# Standard_Header.net
KiCad netlist of a schematic drawn in Altium Designer
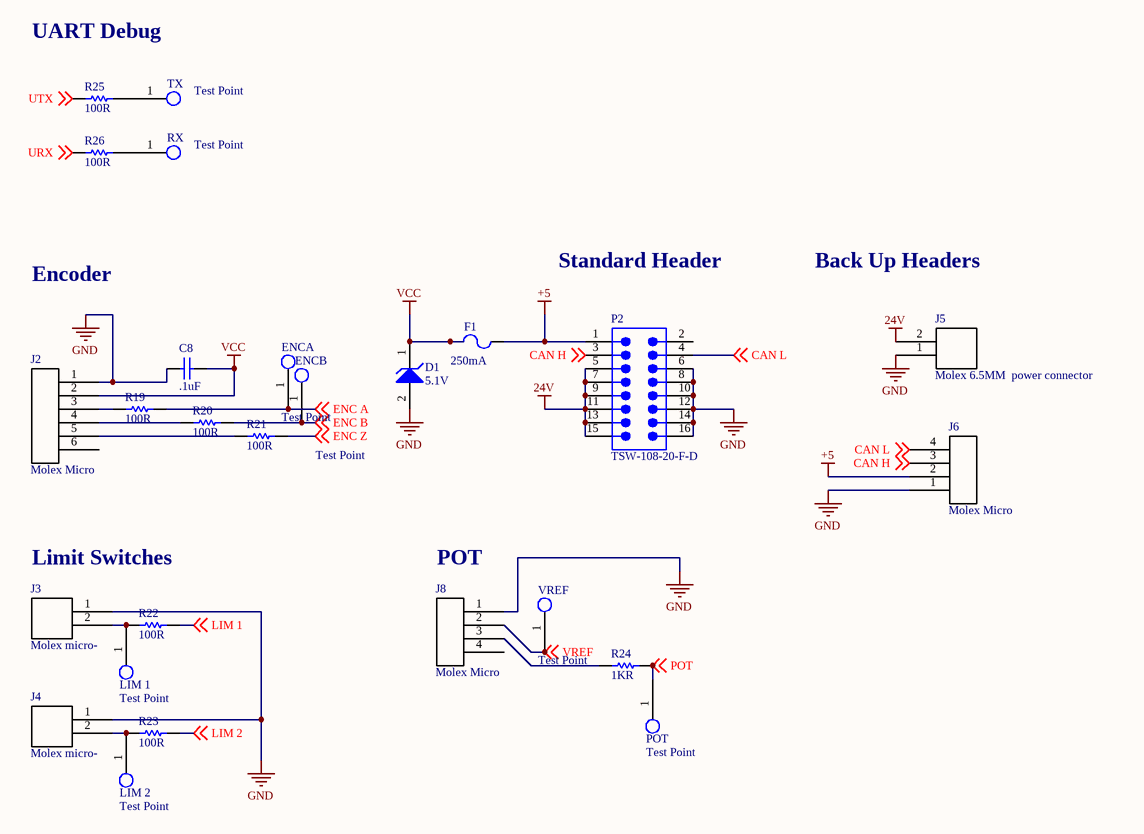
[diagram p0: Standard Header.SchDoc]

(export (version "E")
  (design (tool "Eeschema 10.0.6"))
  (components
    (comp (ref "C8")
      (value ".1uF")
      (footprint "CAPC0805(2012)130_N")
      (description "CAP 390pF 200V ±5% 0805 (2012 Metric) Thickness 1.3mm SMD")
      (fields (field (name "TOLERANCE") "Â±5%"))
      (libsource (lib "Altium Content Vault") (part "CAP"))
    )
    (comp (ref "D1")
      (value "5.1V")
      (footprint "ONSC-SMB-2-403A-03_H_V")
      (description "3 W Zener Voltage Regulator, 2-Pin SMB, Pb-Free, Tape and Reel")
      (fields (field (name "PARTNUMBER") "1SMB5917BT3G") (field (name "MANUFACTURER") "On Semiconductor"))
      (libsource (lib "Husky Robotics Standard Library 2019-2020") (part "CMP-1060-00195-1"))
    )
    (comp (ref "ENCA")
      (value "Test Point")
      (footprint "Test Point Through-hole")
      (libsource (lib "Husky Robotics Standard Library 2019-2020") (part "Test Point"))
    )
    (comp (ref "ENCB")
      (value "Test Point")
      (footprint "Test Point Through-hole")
      (libsource (lib "Husky Robotics Standard Library 2019-2020") (part "Test Point"))
    )
    (comp (ref "F1")
      (value "250mA")
      (footprint "BOUR-MF-NSMF150-2_V")
      (description "PTC Resettable Fuse, 6 V, 100 A, -40 to 85 degC, 2-Pin SMD, RoHS, Tape and Reel")
      (fields (field (name "MANUFACTURER") "Bourns"))
      (libsource (lib "Altium Content Vault") (part "FUSE-2"))
    )
    (comp (ref "J2")
      (value "Molex Micro")
      (footprint "0430450627")
      (description "Molex micro-fit 3.0 dual row connector. P/N 0430450627")
      (libsource (lib "Husky Robotics Standard Library 2019-2020") (part "Molex micro-fit 6-pin (single row schematic)"))
    )
    (comp (ref "J3")
      (value "Molex micro-")
      (footprint "0430450227")
      (description "Molex micro-fit 3.0. Molex P/N 0430450227")
      (libsource (lib "Husky Robotics Standard Library 2019-2020") (part "Molex micro-fit 2-pin"))
    )
    (comp (ref "J4")
      (value "Molex micro-")
      (footprint "0430450227")
      (description "Molex micro-fit 3.0. Molex P/N 0430450227")
      (libsource (lib "Husky Robotics Standard Library 2019-2020") (part "Molex micro-fit 2-pin"))
    )
    (comp (ref "J5")
      (value "Molex 6.5MM  power connector")
      (footprint "1510482204")
      (libsource (lib "Husky Robotics Standard Library 2019-2020") (part "Molex 6.5MM  power connector"))
    )
    (comp (ref "J6")
      (value "Molex Micro")
      (footprint "0430450427")
      (description "Molex micro-fit 3.0 dual row header. P/N 0430450427")
      (libsource (lib "Husky Robotics Standard Library 2019-2020") (part "Molex micro-fit 4-pin (Single row schematic)"))
    )
    (comp (ref "J8")
      (value "Molex Micro")
      (footprint "0430450427")
      (description "Molex micro-fit 3.0 dual row header. P/N 0430450427")
      (libsource (lib "Husky Robotics Standard Library 2019-2020") (part "Molex micro-fit 4-pin (Single row schematic)"))
    )
    (comp (ref "LIM 1")
      (value "Test Point")
      (footprint "Test Point Through-hole")
      (libsource (lib "Husky Robotics Standard Library 2019-2020") (part "Test Point"))
    )
    (comp (ref "LIM 2")
      (value "Test Point")
      (footprint "Test Point Through-hole")
      (libsource (lib "Husky Robotics Standard Library 2019-2020") (part "Test Point"))
    )
    (comp (ref "P2")
      (value "TSW-108-20-F-D")
      (footprint "SMTC-TSW-108-20-X-D")
      (fields (field (name "MANUFACTURER") "Samtec"))
      (libsource (lib "Altium Content Vault") (part "SMTC-TSW-108-X-X-D"))
    )
    (comp (ref "POT")
      (value "Test Point")
      (footprint "Test Point Through-hole")
      (libsource (lib "Husky Robotics Standard Library 2019-2020") (part "Test Point"))
    )
    (comp (ref "R19")
      (value "100R")
      (footprint "RESC0805(2012)_N")
      (description "120R 0.125W 5% 0805 (2012 Metric)  SMD")
      (fields (field (name "TOLERANCE") "5 %") (field (name "POWER") "0.125 W"))
      (libsource (lib "Husky Robotics Standard Library 2019-2020") (part "120R 5% 0805"))
    )
    (comp (ref "R20")
      (value "100R")
      (footprint "RESC0805(2012)_N")
      (description "120R 0.125W 5% 0805 (2012 Metric)  SMD")
      (fields (field (name "TOLERANCE") "5 %") (field (name "POWER") "0.125 W"))
      (libsource (lib "Husky Robotics Standard Library 2019-2020") (part "120R 5% 0805"))
    )
    (comp (ref "R21")
      (value "100R")
      (footprint "RESC0805(2012)_N")
      (description "120R 0.125W 5% 0805 (2012 Metric)  SMD")
      (fields (field (name "TOLERANCE") "5 %") (field (name "POWER") "0.125 W"))
      (libsource (lib "Husky Robotics Standard Library 2019-2020") (part "120R 5% 0805"))
    )
    (comp (ref "R22")
      (value "100R")
      (footprint "RESC0805(2012)_N")
      (description "120R 0.125W 5% 0805 (2012 Metric)  SMD")
      (fields (field (name "TOLERANCE") "5 %") (field (name "POWER") "0.125 W"))
      (libsource (lib "Husky Robotics Standard Library 2019-2020") (part "120R 5% 0805"))
    )
    (comp (ref "R23")
      (value "100R")
      (footprint "RESC0805(2012)_N")
      (description "120R 0.125W 5% 0805 (2012 Metric)  SMD")
      (fields (field (name "TOLERANCE") "5 %") (field (name "POWER") "0.125 W"))
      (libsource (lib "Husky Robotics Standard Library 2019-2020") (part "120R 5% 0805"))
    )
    (comp (ref "R24")
      (value "1KR")
      (footprint "RESC0805(2012)_N")
      (fields (field (name "TOLERANCE") "5 %") (field (name "POWER") "0.125 W"))
      (libsource (lib "Husky Robotics Standard Library 2019-2020") (part "120R 5% 0805"))
    )
    (comp (ref "R25")
      (value "100R")
      (footprint "RESC0805(2012)_N")
      (description "120R 0.125W 5% 0805 (2012 Metric)  SMD")
      (fields (field (name "TOLERANCE") "5 %") (field (name "POWER") "0.125 W"))
      (libsource (lib "Husky Robotics Standard Library 2019-2020") (part "120R 5% 0805"))
    )
    (comp (ref "R26")
      (value "100R")
      (footprint "RESC0805(2012)_N")
      (description "120R 0.125W 5% 0805 (2012 Metric)  SMD")
      (fields (field (name "TOLERANCE") "5 %") (field (name "POWER") "0.125 W"))
      (libsource (lib "Husky Robotics Standard Library 2019-2020") (part "120R 5% 0805"))
    )
    (comp (ref "RX")
      (value "Test Point")
      (footprint "Test Point Through-hole")
      (libsource (lib "Husky Robotics Standard Library 2019-2020") (part "Test Point"))
    )
    (comp (ref "TX")
      (value "Test Point")
      (footprint "Test Point Through-hole")
      (libsource (lib "Husky Robotics Standard Library 2019-2020") (part "Test Point"))
    )
    (comp (ref "VREF")
      (value "Test Point")
      (footprint "Test Point Through-hole")
      (libsource (lib "Husky Robotics Standard Library 2019-2020") (part "Test Point"))
    )
  )
  (nets
    (net (code "1") (name "+5") (class "Default")
      (node (ref "F1") (pin "2") (pinfunction "2_2") (pintype "passive"))
      (node (ref "J6") (pin "2") (pintype "passive"))
      (node (ref "P2") (pin "1") (pinfunction "1_1") (pintype "passive"))
    )
    (net (code "2") (name "24V") (class "Default")
      (node (ref "J5") (pin "2") (pintype "passive"))
      (node (ref "P2") (pin "11") (pinfunction "11_11") (pintype "passive"))
      (node (ref "P2") (pin "13") (pinfunction "13_13") (pintype "passive"))
      (node (ref "P2") (pin "15") (pinfunction "15_15") (pintype "passive"))
      (node (ref "P2") (pin "5") (pinfunction "5_5") (pintype "passive"))
      (node (ref "P2") (pin "7") (pinfunction "7_7") (pintype "passive"))
      (node (ref "P2") (pin "9") (pinfunction "9_9") (pintype "passive"))
    )
    (net (code "3") (name "CAN H") (class "Default")
      (node (ref "J6") (pin "3") (pintype "passive"))
      (node (ref "P2") (pin "3") (pinfunction "3_3") (pintype "passive"))
    )
    (net (code "4") (name "CAN L") (class "Default")
      (node (ref "J6") (pin "4") (pintype "passive"))
      (node (ref "P2") (pin "4") (pinfunction "4_4") (pintype "passive"))
    )
    (net (code "5") (name "ENC A") (class "Default")
      (node (ref "ENCA") (pin "1") (pinfunction "1_1") (pintype "passive"))
      (node (ref "R19") (pin "2") (pinfunction "2_2") (pintype "passive"))
    )
    (net (code "6") (name "ENC B") (class "Default")
      (node (ref "ENCB") (pin "1") (pinfunction "1_1") (pintype "passive"))
      (node (ref "R20") (pin "2") (pinfunction "2_2") (pintype "passive"))
    )
    (net (code "7") (name "ENC Z") (class "Default")
      (node (ref "R21") (pin "2") (pinfunction "2_2") (pintype "passive"))
    )
    (net (code "8") (name "GND") (class "Default")
      (node (ref "C8") (pin "2") (pinfunction "2_2") (pintype "passive"))
      (node (ref "D1") (pin "2") (pinfunction "A_2") (pintype "passive"))
      (node (ref "J2") (pin "1") (pintype "passive"))
      (node (ref "J3") (pin "1") (pintype "passive"))
      (node (ref "J4") (pin "1") (pintype "passive"))
      (node (ref "J5") (pin "1") (pintype "passive"))
      (node (ref "J6") (pin "1") (pintype "passive"))
      (node (ref "J8") (pin "1") (pintype "passive"))
      (node (ref "P2") (pin "10") (pinfunction "10_10") (pintype "passive"))
      (node (ref "P2") (pin "12") (pinfunction "12_12") (pintype "passive"))
      (node (ref "P2") (pin "14") (pinfunction "14_14") (pintype "passive"))
      (node (ref "P2") (pin "16") (pinfunction "16_16") (pintype "passive"))
      (node (ref "P2") (pin "6") (pinfunction "6_6") (pintype "passive"))
      (node (ref "P2") (pin "8") (pinfunction "8_8") (pintype "passive"))
    )
    (net (code "9") (name "LIM 1") (class "Default")
      (node (ref "R22") (pin "2") (pinfunction "2_2") (pintype "passive"))
    )
    (net (code "10") (name "LIM 2") (class "Default")
      (node (ref "R23") (pin "2") (pinfunction "2_2") (pintype "passive"))
    )
    (net (code "11") (name "Net-(J2-Pad3)") (class "Default")
      (node (ref "J2") (pin "3") (pintype "passive"))
      (node (ref "R19") (pin "1") (pinfunction "1_1") (pintype "passive"))
    )
    (net (code "12") (name "Net-(J2-Pad4)") (class "Default")
      (node (ref "J2") (pin "4") (pintype "passive"))
      (node (ref "R20") (pin "1") (pinfunction "1_1") (pintype "passive"))
    )
    (net (code "13") (name "Net-(J2-Pad5)") (class "Default")
      (node (ref "J2") (pin "5") (pintype "passive"))
      (node (ref "R21") (pin "1") (pinfunction "1_1") (pintype "passive"))
    )
    (net (code "14") (name "Net-(J3-Pad2)") (class "Default")
      (node (ref "J3") (pin "2") (pintype "passive"))
      (node (ref "LIM 1") (pin "1") (pinfunction "1_1") (pintype "passive"))
      (node (ref "R22") (pin "1") (pinfunction "1_1") (pintype "passive"))
    )
    (net (code "15") (name "Net-(J4-Pad2)") (class "Default")
      (node (ref "J4") (pin "2") (pintype "passive"))
      (node (ref "LIM 2") (pin "1") (pinfunction "1_1") (pintype "passive"))
      (node (ref "R23") (pin "1") (pinfunction "1_1") (pintype "passive"))
    )
    (net (code "16") (name "Net-(J8-Pad3)") (class "Default")
      (node (ref "J8") (pin "3") (pintype "passive"))
      (node (ref "R24") (pin "1") (pinfunction "1_1") (pintype "passive"))
    )
    (net (code "17") (name "Net-(R25-Pad2)") (class "Default")
      (node (ref "R25") (pin "2") (pinfunction "2_2") (pintype "passive"))
      (node (ref "TX") (pin "1") (pinfunction "1_1") (pintype "passive"))
    )
    (net (code "18") (name "Net-(R26-Pad2)") (class "Default")
      (node (ref "R26") (pin "2") (pinfunction "2_2") (pintype "passive"))
      (node (ref "RX") (pin "1") (pinfunction "1_1") (pintype "passive"))
    )
    (net (code "19") (name "POT") (class "Default")
      (node (ref "POT") (pin "1") (pinfunction "1_1") (pintype "passive"))
      (node (ref "R24") (pin "2") (pinfunction "2_2") (pintype "passive"))
    )
    (net (code "20") (name "URX") (class "Default")
      (node (ref "R26") (pin "1") (pinfunction "1_1") (pintype "passive"))
    )
    (net (code "21") (name "UTX") (class "Default")
      (node (ref "R25") (pin "1") (pinfunction "1_1") (pintype "passive"))
    )
    (net (code "22") (name "VCC") (class "Default")
      (node (ref "C8") (pin "1") (pinfunction "1_1") (pintype "passive"))
      (node (ref "D1") (pin "1") (pinfunction "K_1") (pintype "passive"))
      (node (ref "F1") (pin "1") (pinfunction "1_1") (pintype "passive"))
      (node (ref "J2") (pin "2") (pintype "passive"))
    )
    (net (code "23") (name "VREF") (class "Default")
      (node (ref "J8") (pin "2") (pintype "passive"))
      (node (ref "VREF") (pin "1") (pinfunction "1_1") (pintype "passive"))
    )
    (net (code "24") (name "unconnected-(J2-Pad6)") (class "Default")
      (node (ref "J2") (pin "6") (pintype "passive"))
    )
    (net (code "25") (name "unconnected-(J8-Pad4)") (class "Default")
      (node (ref "J8") (pin "4") (pintype "passive"))
    )
    (net (code "26") (name "unconnected-(P2-Pad2)") (class "Default")
      (node (ref "P2") (pin "2") (pinfunction "2_2") (pintype "passive"))
    )
  )
)
